# cdf-modular-bridge-rev3.net
KiCad netlist of a schematic drawn in EAGLE
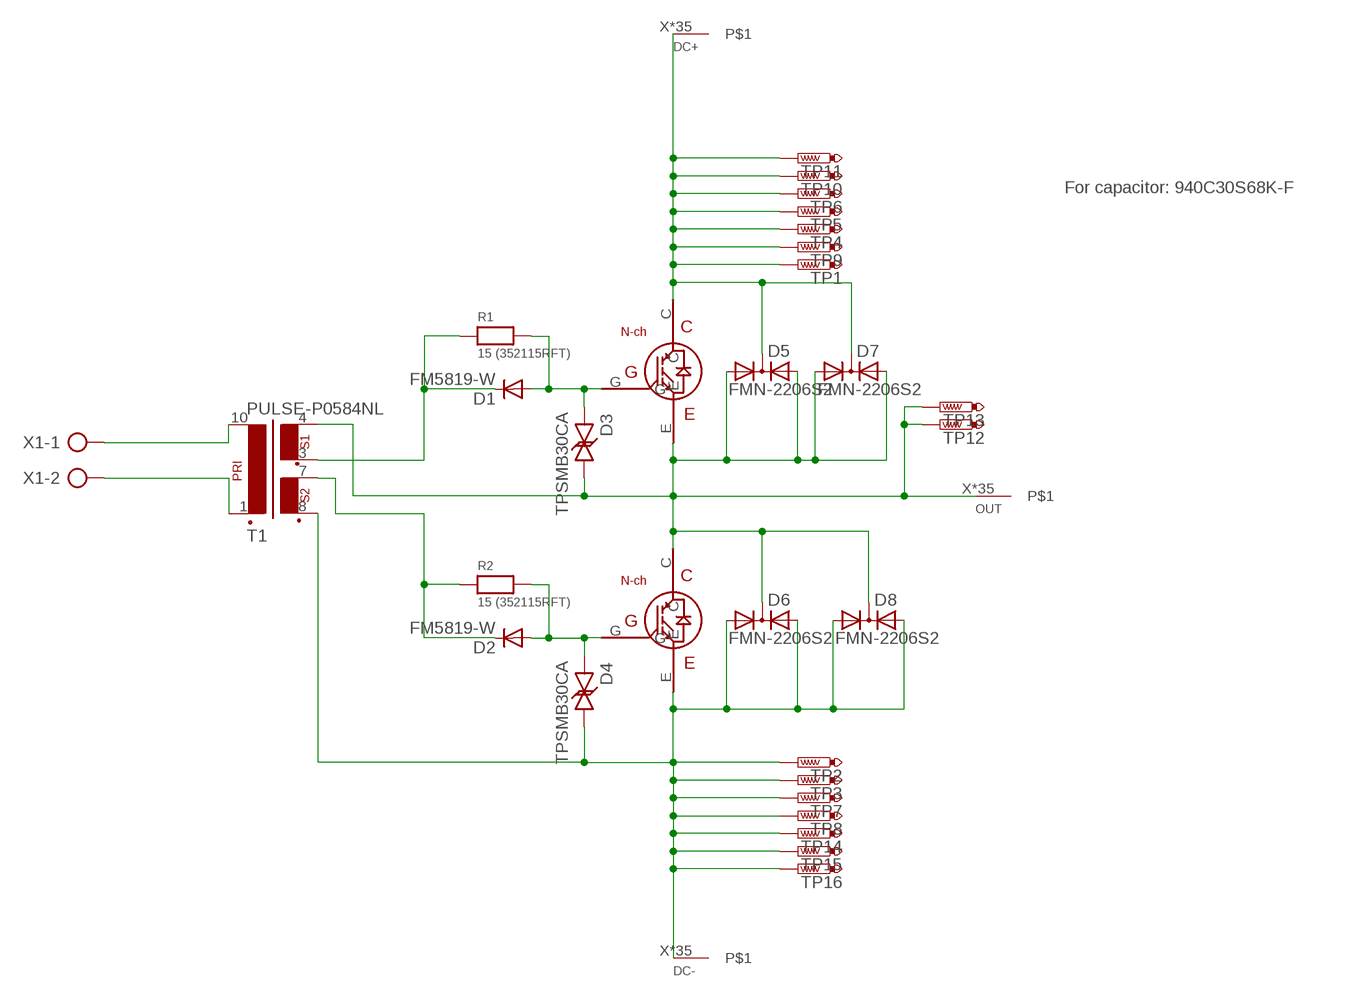
[diagram p0: schematic, sheet 1]

(export (version "E")
  (design (tool "Eeschema 10.0.6"))
  (components
    (comp (ref "D1")
      (value "FM5819-W")
      (footprint "eagle-import:DO214AC")
      (fields (field (name "MF") "Fairchild") (field (name "MPN") "S1A"))
      (libsource (lib "eagle-import") (part "S1A"))
    )
    (comp (ref "D2")
      (value "FM5819-W")
      (footprint "eagle-import:DO214AC")
      (fields (field (name "MF") "Fairchild") (field (name "MPN") "S1A"))
      (libsource (lib "eagle-import") (part "S1A"))
    )
    (comp (ref "D3")
      (value "TPSMB30CA")
      (footprint "eagle-import:TPSMB15CA")
      (libsource (lib "eagle-import") (part "TPSMB15CA"))
    )
    (comp (ref "D4")
      (value "TPSMB30CA")
      (footprint "eagle-import:TPSMB15CA")
      (libsource (lib "eagle-import") (part "TPSMB15CA"))
    )
    (comp (ref "D5")
      (value "FMN-2206S2")
      (footprint "eagle-import:TO220-CDF-SPACED-LEGS")
      (libsource (lib "eagle-import") (part "FMN-2206S2"))
    )
    (comp (ref "D6")
      (value "FMN-2206S2")
      (footprint "eagle-import:TO220-CDF-SPACED-LEGS")
      (libsource (lib "eagle-import") (part "FMN-2206S2"))
    )
    (comp (ref "D7")
      (value "FMN-2206S2")
      (footprint "eagle-import:TO220-CDF-SPACED-LEGS")
      (libsource (lib "eagle-import") (part "FMN-2206S2"))
    )
    (comp (ref "D8")
      (value "FMN-2206S2")
      (footprint "eagle-import:TO220-CDF-SPACED-LEGS")
      (libsource (lib "eagle-import") (part "FMN-2206S2"))
    )
    (comp (ref "DC+")
      (value "BIG-ASS-HOLE")
      (footprint "eagle-import:BIG-ASS-HOLE")
      (libsource (lib "eagle-import") (part "BIG-ASS-HOLE"))
    )
    (comp (ref "DC-")
      (value "BIG-ASS-HOLE")
      (footprint "eagle-import:BIG-ASS-HOLE")
      (libsource (lib "eagle-import") (part "BIG-ASS-HOLE"))
    )
    (comp (ref "OUT")
      (value "BIG-ASS-HOLE")
      (footprint "eagle-import:BIG-ASS-HOLE")
      (libsource (lib "eagle-import") (part "BIG-ASS-HOLE"))
    )
    (comp (ref "Q1")
      (value "Ixgh48n60a3")
      (footprint "eagle-import:IXGH40N60A")
      (libsource (lib "eagle-import") (part "IXGH40N60A"))
    )
    (comp (ref "Q2")
      (value "Ixgh48n60a3")
      (footprint "eagle-import:IXGH40N60A")
      (libsource (lib "eagle-import") (part "IXGH40N60A"))
    )
    (comp (ref "R1")
      (value "15 (352115RFT)")
      (footprint "eagle-import:2512")
      (libsource (lib "eagle-import") (part "RESISTOR2512"))
    )
    (comp (ref "R2")
      (value "15 (352115RFT)")
      (footprint "eagle-import:2512")
      (libsource (lib "eagle-import") (part "RESISTOR2512"))
    )
    (comp (ref "T1")
      (value "PULSE-P0584NL")
      (footprint "eagle-import:PULSE-P0584NL")
      (libsource (lib "eagle-import") (part "PULSE-P0584NL"))
    )
    (comp (ref "TP1")
      (value "PTR1PAD1-17")
      (footprint "eagle-import:P1-17")
      (libsource (lib "eagle-import") (part "PTR1PAD1-17"))
    )
    (comp (ref "TP2")
      (value "PTR1PAD1-17")
      (footprint "eagle-import:P1-17")
      (libsource (lib "eagle-import") (part "PTR1PAD1-17"))
    )
    (comp (ref "TP3")
      (value "PTR1PAD1-17")
      (footprint "eagle-import:P1-17")
      (libsource (lib "eagle-import") (part "PTR1PAD1-17"))
    )
    (comp (ref "TP4")
      (value "PTR1PAD1-17")
      (footprint "eagle-import:P1-17")
      (libsource (lib "eagle-import") (part "PTR1PAD1-17"))
    )
    (comp (ref "TP5")
      (value "PTR1PAD1-17")
      (footprint "eagle-import:P1-17")
      (libsource (lib "eagle-import") (part "PTR1PAD1-17"))
    )
    (comp (ref "TP6")
      (value "PTR1PAD1-17")
      (footprint "eagle-import:P1-17")
      (libsource (lib "eagle-import") (part "PTR1PAD1-17"))
    )
    (comp (ref "TP7")
      (value "PTR1PAD1-17")
      (footprint "eagle-import:P1-17")
      (libsource (lib "eagle-import") (part "PTR1PAD1-17"))
    )
    (comp (ref "TP8")
      (value "PTR1PAD1-17")
      (footprint "eagle-import:P1-17")
      (libsource (lib "eagle-import") (part "PTR1PAD1-17"))
    )
    (comp (ref "TP9")
      (value "PTR1PAD1-17")
      (footprint "eagle-import:P1-17")
      (libsource (lib "eagle-import") (part "PTR1PAD1-17"))
    )
    (comp (ref "TP10")
      (value "PTR1PAD1-17")
      (footprint "eagle-import:P1-17")
      (libsource (lib "eagle-import") (part "PTR1PAD1-17"))
    )
    (comp (ref "TP11")
      (value "PTR1PAD1-17")
      (footprint "eagle-import:P1-17")
      (libsource (lib "eagle-import") (part "PTR1PAD1-17"))
    )
    (comp (ref "TP12")
      (value "PTR1PAD1-17")
      (footprint "eagle-import:P1-17")
      (libsource (lib "eagle-import") (part "PTR1PAD1-17"))
    )
    (comp (ref "TP13")
      (value "PTR1PAD1-17")
      (footprint "eagle-import:P1-17")
      (libsource (lib "eagle-import") (part "PTR1PAD1-17"))
    )
    (comp (ref "TP14")
      (value "PTR1PAD1-17")
      (footprint "eagle-import:P1-17")
      (libsource (lib "eagle-import") (part "PTR1PAD1-17"))
    )
    (comp (ref "TP15")
      (value "PTR1PAD1-17")
      (footprint "eagle-import:P1-17")
      (libsource (lib "eagle-import") (part "PTR1PAD1-17"))
    )
    (comp (ref "TP16")
      (value "PTR1PAD1-17")
      (footprint "eagle-import:P1-17")
      (libsource (lib "eagle-import") (part "PTR1PAD1-17"))
    )
    (comp (ref "X1")
      (value "AK500/2")
      (footprint "eagle-import:AK500_2")
      (libsource (lib "eagle-import") (part "AK500/2"))
    )
  )
  (nets
    (net (code "1") (name "Net-(D1-PadA)") (class "Default")
      (node (ref "D1") (pin "A") (pinfunction "A_A") (pintype "passive"))
      (node (ref "D3") (pin "P$1") (pinfunction "P$1_P$1") (pintype "passive"))
      (node (ref "Q1") (pin "G") (pinfunction "G_G") (pintype "bidirectional"))
      (node (ref "R1") (pin "2") (pinfunction "2_2") (pintype "passive"))
    )
    (net (code "2") (name "Net-(D2-PadA)") (class "Default")
      (node (ref "D2") (pin "A") (pinfunction "A_A") (pintype "passive"))
      (node (ref "D4") (pin "P$1") (pinfunction "P$1_P$1") (pintype "passive"))
      (node (ref "Q2") (pin "G") (pinfunction "G_G") (pintype "bidirectional"))
      (node (ref "R2") (pin "2") (pinfunction "2_2") (pintype "passive"))
    )
    (net (code "3") (name "Net-(D5-PadC)") (class "Default")
      (node (ref "D5") (pin "C") (pinfunction "C_C") (pintype "passive"))
      (node (ref "D7") (pin "C") (pinfunction "C_C") (pintype "passive"))
      (node (ref "DC+") (pin "X") (pinfunction "P$1_X") (pintype "bidirectional"))
      (node (ref "DC+") (pin "X@1") (pinfunction "P$1_X@1") (pintype "bidirectional"))
      (node (ref "DC+") (pin "X@10") (pinfunction "P$1_X@10") (pintype "bidirectional"))
      (node (ref "DC+") (pin "X@11") (pinfunction "P$1_X@11") (pintype "bidirectional"))
      (node (ref "DC+") (pin "X@12") (pinfunction "P$1_X@12") (pintype "bidirectional"))
      (node (ref "DC+") (pin "X@120") (pinfunction "P$1_X@120") (pintype "bidirectional"))
      (node (ref "DC+") (pin "X@13") (pinfunction "P$1_X@13") (pintype "bidirectional"))
      (node (ref "DC+") (pin "X@14") (pinfunction "P$1_X@14") (pintype "bidirectional"))
      (node (ref "DC+") (pin "X@15") (pinfunction "P$1_X@15") (pintype "bidirectional"))
      (node (ref "DC+") (pin "X@16") (pinfunction "P$1_X@16") (pintype "bidirectional"))
      (node (ref "DC+") (pin "X@17") (pinfunction "P$1_X@17") (pintype "bidirectional"))
      (node (ref "DC+") (pin "X@18") (pinfunction "P$1_X@18") (pintype "bidirectional"))
      (node (ref "DC+") (pin "X@19") (pinfunction "P$1_X@19") (pintype "bidirectional"))
      (node (ref "DC+") (pin "X@2") (pinfunction "P$1_X@2") (pintype "bidirectional"))
      (node (ref "DC+") (pin "X@20") (pinfunction "P$1_X@20") (pintype "bidirectional"))
      (node (ref "DC+") (pin "X@21") (pinfunction "P$1_X@21") (pintype "bidirectional"))
      (node (ref "DC+") (pin "X@22") (pinfunction "P$1_X@22") (pintype "bidirectional"))
      (node (ref "DC+") (pin "X@23") (pinfunction "P$1_X@23") (pintype "bidirectional"))
      (node (ref "DC+") (pin "X@24") (pinfunction "P$1_X@24") (pintype "bidirectional"))
      (node (ref "DC+") (pin "X@25") (pinfunction "P$1_X@25") (pintype "bidirectional"))
      (node (ref "DC+") (pin "X@26") (pinfunction "P$1_X@26") (pintype "bidirectional"))
      (node (ref "DC+") (pin "X@27") (pinfunction "P$1_X@27") (pintype "bidirectional"))
      (node (ref "DC+") (pin "X@28") (pinfunction "P$1_X@28") (pintype "bidirectional"))
      (node (ref "DC+") (pin "X@29") (pinfunction "P$1_X@29") (pintype "bidirectional"))
      (node (ref "DC+") (pin "X@3") (pinfunction "P$1_X@3") (pintype "bidirectional"))
      (node (ref "DC+") (pin "X@30") (pinfunction "P$1_X@30") (pintype "bidirectional"))
      (node (ref "DC+") (pin "X@31") (pinfunction "P$1_X@31") (pintype "bidirectional"))
      (node (ref "DC+") (pin "X@32") (pinfunction "P$1_X@32") (pintype "bidirectional"))
      (node (ref "DC+") (pin "X@34") (pinfunction "P$1_X@34") (pintype "bidirectional"))
      (node (ref "DC+") (pin "X@4") (pinfunction "P$1_X@4") (pintype "bidirectional"))
      (node (ref "DC+") (pin "X@5") (pinfunction "P$1_X@5") (pintype "bidirectional"))
      (node (ref "DC+") (pin "X@6") (pinfunction "P$1_X@6") (pintype "bidirectional"))
      (node (ref "DC+") (pin "X@7") (pinfunction "P$1_X@7") (pintype "bidirectional"))
      (node (ref "DC+") (pin "X@8") (pinfunction "P$1_X@8") (pintype "bidirectional"))
      (node (ref "DC+") (pin "X@9") (pinfunction "P$1_X@9") (pintype "bidirectional"))
      (node (ref "Q1") (pin "C") (pinfunction "C_C") (pintype "bidirectional"))
      (node (ref "TP1") (pin "TP") (pinfunction "TP_TP") (pintype "input"))
      (node (ref "TP10") (pin "TP") (pinfunction "TP_TP") (pintype "input"))
      (node (ref "TP11") (pin "TP") (pinfunction "TP_TP") (pintype "input"))
      (node (ref "TP4") (pin "TP") (pinfunction "TP_TP") (pintype "input"))
      (node (ref "TP5") (pin "TP") (pinfunction "TP_TP") (pintype "input"))
      (node (ref "TP6") (pin "TP") (pinfunction "TP_TP") (pintype "input"))
      (node (ref "TP9") (pin "TP") (pinfunction "TP_TP") (pintype "input"))
    )
    (net (code "4") (name "Net-(T1-PRI_NEG)") (class "Default")
      (node (ref "T1") (pin "10") (pinfunction "PRI_NEG_10") (pintype "passive"))
      (node (ref "X1") (pin "1") (pinfunction "KL_1") (pintype "passive"))
    )
    (net (code "5") (name "Net-(T1-PRI_POS)") (class "Default")
      (node (ref "T1") (pin "1") (pinfunction "PRI_POS_1") (pintype "passive"))
      (node (ref "X1") (pin "2") (pinfunction "KL_2") (pintype "passive"))
    )
    (net (code "6") (name "Net-(T1-SEC1_NEG)") (class "Default")
      (node (ref "D3") (pin "P$2") (pinfunction "P$2_P$2") (pintype "passive"))
      (node (ref "D5") (pin "A1") (pinfunction "A1_A1") (pintype "passive"))
      (node (ref "D5") (pin "A2") (pinfunction "A2_A2") (pintype "passive"))
      (node (ref "D6") (pin "C") (pinfunction "C_C") (pintype "passive"))
      (node (ref "D7") (pin "A1") (pinfunction "A1_A1") (pintype "passive"))
      (node (ref "D7") (pin "A2") (pinfunction "A2_A2") (pintype "passive"))
      (node (ref "D8") (pin "C") (pinfunction "C_C") (pintype "passive"))
      (node (ref "OUT") (pin "X") (pinfunction "P$1_X") (pintype "bidirectional"))
      (node (ref "OUT") (pin "X@1") (pinfunction "P$1_X@1") (pintype "bidirectional"))
      (node (ref "OUT") (pin "X@10") (pinfunction "P$1_X@10") (pintype "bidirectional"))
      (node (ref "OUT") (pin "X@11") (pinfunction "P$1_X@11") (pintype "bidirectional"))
      (node (ref "OUT") (pin "X@12") (pinfunction "P$1_X@12") (pintype "bidirectional"))
      (node (ref "OUT") (pin "X@120") (pinfunction "P$1_X@120") (pintype "bidirectional"))
      (node (ref "OUT") (pin "X@13") (pinfunction "P$1_X@13") (pintype "bidirectional"))
      (node (ref "OUT") (pin "X@14") (pinfunction "P$1_X@14") (pintype "bidirectional"))
      (node (ref "OUT") (pin "X@15") (pinfunction "P$1_X@15") (pintype "bidirectional"))
      (node (ref "OUT") (pin "X@16") (pinfunction "P$1_X@16") (pintype "bidirectional"))
      (node (ref "OUT") (pin "X@17") (pinfunction "P$1_X@17") (pintype "bidirectional"))
      (node (ref "OUT") (pin "X@18") (pinfunction "P$1_X@18") (pintype "bidirectional"))
      (node (ref "OUT") (pin "X@19") (pinfunction "P$1_X@19") (pintype "bidirectional"))
      (node (ref "OUT") (pin "X@2") (pinfunction "P$1_X@2") (pintype "bidirectional"))
      (node (ref "OUT") (pin "X@20") (pinfunction "P$1_X@20") (pintype "bidirectional"))
      (node (ref "OUT") (pin "X@21") (pinfunction "P$1_X@21") (pintype "bidirectional"))
      (node (ref "OUT") (pin "X@22") (pinfunction "P$1_X@22") (pintype "bidirectional"))
      (node (ref "OUT") (pin "X@23") (pinfunction "P$1_X@23") (pintype "bidirectional"))
      (node (ref "OUT") (pin "X@24") (pinfunction "P$1_X@24") (pintype "bidirectional"))
      (node (ref "OUT") (pin "X@25") (pinfunction "P$1_X@25") (pintype "bidirectional"))
      (node (ref "OUT") (pin "X@26") (pinfunction "P$1_X@26") (pintype "bidirectional"))
      (node (ref "OUT") (pin "X@27") (pinfunction "P$1_X@27") (pintype "bidirectional"))
      (node (ref "OUT") (pin "X@28") (pinfunction "P$1_X@28") (pintype "bidirectional"))
      (node (ref "OUT") (pin "X@29") (pinfunction "P$1_X@29") (pintype "bidirectional"))
      (node (ref "OUT") (pin "X@3") (pinfunction "P$1_X@3") (pintype "bidirectional"))
      (node (ref "OUT") (pin "X@30") (pinfunction "P$1_X@30") (pintype "bidirectional"))
      (node (ref "OUT") (pin "X@31") (pinfunction "P$1_X@31") (pintype "bidirectional"))
      (node (ref "OUT") (pin "X@32") (pinfunction "P$1_X@32") (pintype "bidirectional"))
      (node (ref "OUT") (pin "X@34") (pinfunction "P$1_X@34") (pintype "bidirectional"))
      (node (ref "OUT") (pin "X@4") (pinfunction "P$1_X@4") (pintype "bidirectional"))
      (node (ref "OUT") (pin "X@5") (pinfunction "P$1_X@5") (pintype "bidirectional"))
      (node (ref "OUT") (pin "X@6") (pinfunction "P$1_X@6") (pintype "bidirectional"))
      (node (ref "OUT") (pin "X@7") (pinfunction "P$1_X@7") (pintype "bidirectional"))
      (node (ref "OUT") (pin "X@8") (pinfunction "P$1_X@8") (pintype "bidirectional"))
      (node (ref "OUT") (pin "X@9") (pinfunction "P$1_X@9") (pintype "bidirectional"))
      (node (ref "Q1") (pin "E") (pinfunction "E_E") (pintype "bidirectional"))
      (node (ref "Q2") (pin "C") (pinfunction "C_C") (pintype "bidirectional"))
      (node (ref "T1") (pin "4") (pinfunction "SEC1_NEG_4") (pintype "passive"))
      (node (ref "TP12") (pin "TP") (pinfunction "TP_TP") (pintype "input"))
      (node (ref "TP13") (pin "TP") (pinfunction "TP_TP") (pintype "input"))
    )
    (net (code "7") (name "Net-(T1-SEC1_POS)") (class "Default")
      (node (ref "D1") (pin "C") (pinfunction "C_C") (pintype "passive"))
      (node (ref "R1") (pin "1") (pinfunction "1_1") (pintype "passive"))
      (node (ref "T1") (pin "3") (pinfunction "SEC1_POS_3") (pintype "passive"))
    )
    (net (code "8") (name "Net-(T1-SEC2_NEG)") (class "Default")
      (node (ref "D2") (pin "C") (pinfunction "C_C") (pintype "passive"))
      (node (ref "R2") (pin "1") (pinfunction "1_1") (pintype "passive"))
      (node (ref "T1") (pin "7") (pinfunction "SEC2_NEG_7") (pintype "passive"))
    )
    (net (code "9") (name "Net-(T1-SEC2_POS)") (class "Default")
      (node (ref "D4") (pin "P$2") (pinfunction "P$2_P$2") (pintype "passive"))
      (node (ref "D6") (pin "A1") (pinfunction "A1_A1") (pintype "passive"))
      (node (ref "D6") (pin "A2") (pinfunction "A2_A2") (pintype "passive"))
      (node (ref "D8") (pin "A1") (pinfunction "A1_A1") (pintype "passive"))
      (node (ref "D8") (pin "A2") (pinfunction "A2_A2") (pintype "passive"))
      (node (ref "DC-") (pin "X") (pinfunction "P$1_X") (pintype "bidirectional"))
      (node (ref "DC-") (pin "X@1") (pinfunction "P$1_X@1") (pintype "bidirectional"))
      (node (ref "DC-") (pin "X@10") (pinfunction "P$1_X@10") (pintype "bidirectional"))
      (node (ref "DC-") (pin "X@11") (pinfunction "P$1_X@11") (pintype "bidirectional"))
      (node (ref "DC-") (pin "X@12") (pinfunction "P$1_X@12") (pintype "bidirectional"))
      (node (ref "DC-") (pin "X@120") (pinfunction "P$1_X@120") (pintype "bidirectional"))
      (node (ref "DC-") (pin "X@13") (pinfunction "P$1_X@13") (pintype "bidirectional"))
      (node (ref "DC-") (pin "X@14") (pinfunction "P$1_X@14") (pintype "bidirectional"))
      (node (ref "DC-") (pin "X@15") (pinfunction "P$1_X@15") (pintype "bidirectional"))
      (node (ref "DC-") (pin "X@16") (pinfunction "P$1_X@16") (pintype "bidirectional"))
      (node (ref "DC-") (pin "X@17") (pinfunction "P$1_X@17") (pintype "bidirectional"))
      (node (ref "DC-") (pin "X@18") (pinfunction "P$1_X@18") (pintype "bidirectional"))
      (node (ref "DC-") (pin "X@19") (pinfunction "P$1_X@19") (pintype "bidirectional"))
      (node (ref "DC-") (pin "X@2") (pinfunction "P$1_X@2") (pintype "bidirectional"))
      (node (ref "DC-") (pin "X@20") (pinfunction "P$1_X@20") (pintype "bidirectional"))
      (node (ref "DC-") (pin "X@21") (pinfunction "P$1_X@21") (pintype "bidirectional"))
      (node (ref "DC-") (pin "X@22") (pinfunction "P$1_X@22") (pintype "bidirectional"))
      (node (ref "DC-") (pin "X@23") (pinfunction "P$1_X@23") (pintype "bidirectional"))
      (node (ref "DC-") (pin "X@24") (pinfunction "P$1_X@24") (pintype "bidirectional"))
      (node (ref "DC-") (pin "X@25") (pinfunction "P$1_X@25") (pintype "bidirectional"))
      (node (ref "DC-") (pin "X@26") (pinfunction "P$1_X@26") (pintype "bidirectional"))
      (node (ref "DC-") (pin "X@27") (pinfunction "P$1_X@27") (pintype "bidirectional"))
      (node (ref "DC-") (pin "X@28") (pinfunction "P$1_X@28") (pintype "bidirectional"))
      (node (ref "DC-") (pin "X@29") (pinfunction "P$1_X@29") (pintype "bidirectional"))
      (node (ref "DC-") (pin "X@3") (pinfunction "P$1_X@3") (pintype "bidirectional"))
      (node (ref "DC-") (pin "X@30") (pinfunction "P$1_X@30") (pintype "bidirectional"))
      (node (ref "DC-") (pin "X@31") (pinfunction "P$1_X@31") (pintype "bidirectional"))
      (node (ref "DC-") (pin "X@32") (pinfunction "P$1_X@32") (pintype "bidirectional"))
      (node (ref "DC-") (pin "X@34") (pinfunction "P$1_X@34") (pintype "bidirectional"))
      (node (ref "DC-") (pin "X@4") (pinfunction "P$1_X@4") (pintype "bidirectional"))
      (node (ref "DC-") (pin "X@5") (pinfunction "P$1_X@5") (pintype "bidirectional"))
      (node (ref "DC-") (pin "X@6") (pinfunction "P$1_X@6") (pintype "bidirectional"))
      (node (ref "DC-") (pin "X@7") (pinfunction "P$1_X@7") (pintype "bidirectional"))
      (node (ref "DC-") (pin "X@8") (pinfunction "P$1_X@8") (pintype "bidirectional"))
      (node (ref "DC-") (pin "X@9") (pinfunction "P$1_X@9") (pintype "bidirectional"))
      (node (ref "Q2") (pin "E") (pinfunction "E_E") (pintype "bidirectional"))
      (node (ref "T1") (pin "8") (pinfunction "SEC2_POS_8") (pintype "passive"))
      (node (ref "TP14") (pin "TP") (pinfunction "TP_TP") (pintype "input"))
      (node (ref "TP15") (pin "TP") (pinfunction "TP_TP") (pintype "input"))
      (node (ref "TP16") (pin "TP") (pinfunction "TP_TP") (pintype "input"))
      (node (ref "TP2") (pin "TP") (pinfunction "TP_TP") (pintype "input"))
      (node (ref "TP3") (pin "TP") (pinfunction "TP_TP") (pintype "input"))
      (node (ref "TP7") (pin "TP") (pinfunction "TP_TP") (pintype "input"))
      (node (ref "TP8") (pin "TP") (pinfunction "TP_TP") (pintype "input"))
    )
  )
)
